# TinyX4.net
KiCad netlist of a schematic drawn in EAGLE
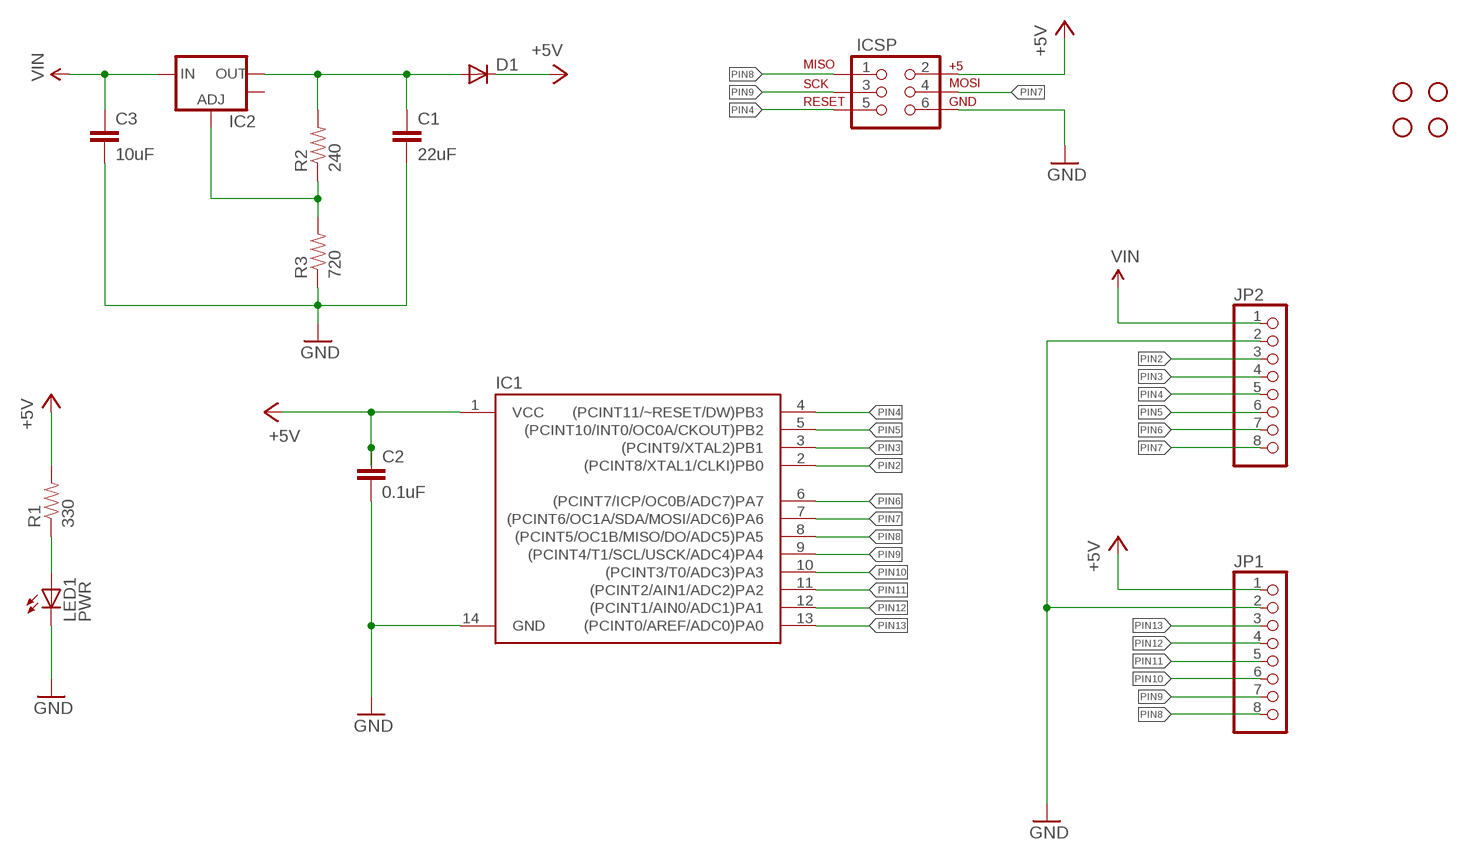
[diagram p0: schematic, sheet 1]

(export (version "E")
  (design (tool "Eeschema 10.0.6"))
  (components
    (comp (ref "C1")
      (value "22uF")
      (footprint "eagle-import:1206")
      (libsource (lib "eagle-import") (part "CAP1206"))
    )
    (comp (ref "C2")
      (value "0.1uF")
      (footprint "eagle-import:1206")
      (libsource (lib "eagle-import") (part "CAP1206"))
    )
    (comp (ref "C3")
      (value "10uF")
      (footprint "eagle-import:1206")
      (libsource (lib "eagle-import") (part "CAP1206"))
    )
    (comp (ref "D1")
      (value "DIODESOD")
      (footprint "eagle-import:SOD-323")
      (libsource (lib "eagle-import") (part "DIODESOD"))
    )
    (comp (ref "IC1")
      (value "ATTINY84ATTINY84-20PU")
      (footprint "eagle-import:DIL14")
      (libsource (lib "eagle-import") (part "ATTINY84ATTINY84-20PU"))
    )
    (comp (ref "IC2")
      (value "V_REG_LM1117SOT223")
      (footprint "eagle-import:SOT223")
      (libsource (lib "eagle-import") (part "V_REG_LM1117SOT223"))
    )
    (comp (ref "ICSP")
      (value "AVR_SPI_PRG_6PTH")
      (footprint "eagle-import:2X3")
      (libsource (lib "eagle-import") (part "AVR_SPI_PRG_6PTH"))
    )
    (comp (ref "JP1")
      (value "PINHD-1X8")
      (footprint "eagle-import:1X08")
      (libsource (lib "eagle-import") (part "PINHD-1X8"))
    )
    (comp (ref "JP2")
      (value "PINHD-1X8")
      (footprint "eagle-import:1X08")
      (libsource (lib "eagle-import") (part "PINHD-1X8"))
    )
    (comp (ref "LED1")
      (value "PWR")
      (footprint "eagle-import:LED-1206")
      (libsource (lib "eagle-import") (part "LED-RED1206"))
    )
    (comp (ref "R1")
      (value "330")
      (footprint "eagle-import:1206")
      (libsource (lib "eagle-import") (part "SparkFun-Resistors_RESISTOR1206"))
    )
    (comp (ref "R2")
      (value "240")
      (footprint "eagle-import:1206")
      (libsource (lib "eagle-import") (part "RESISTOR1206"))
    )
    (comp (ref "R3")
      (value "720")
      (footprint "eagle-import:1206")
      (libsource (lib "eagle-import") (part "RESISTOR1206"))
    )
    (comp (ref "STANDOFF1")
      (value "STAND-OFFTIGHT")
      (footprint "eagle-import:STAND-OFF-TIGHT")
      (libsource (lib "eagle-import") (part "STAND-OFFTIGHT"))
    )
    (comp (ref "STANDOFF2")
      (value "STAND-OFFTIGHT")
      (footprint "eagle-import:STAND-OFF-TIGHT")
      (libsource (lib "eagle-import") (part "STAND-OFFTIGHT"))
    )
    (comp (ref "STANDOFF3")
      (value "STAND-OFFTIGHT")
      (footprint "eagle-import:STAND-OFF-TIGHT")
      (libsource (lib "eagle-import") (part "STAND-OFFTIGHT"))
    )
    (comp (ref "STANDOFF4")
      (value "STAND-OFFTIGHT")
      (footprint "eagle-import:STAND-OFF-TIGHT")
      (libsource (lib "eagle-import") (part "STAND-OFFTIGHT"))
    )
  )
  (nets
    (net (code "1") (name "+5V") (class "Default")
      (node (ref "C2") (pin "1") (pinfunction "1_1") (pintype "passive"))
      (node (ref "D1") (pin "1") (pinfunction "C_1") (pintype "passive"))
      (node (ref "IC1") (pin "1") (pinfunction "VCC_1") (pintype "bidirectional"))
      (node (ref "ICSP") (pin "2") (pinfunction "2_2") (pintype "passive"))
      (node (ref "JP1") (pin "1") (pinfunction "1_1") (pintype "passive"))
      (node (ref "R1") (pin "2") (pinfunction "2_2") (pintype "passive"))
    )
    (net (code "2") (name "GND") (class "Default")
      (node (ref "C1") (pin "2") (pinfunction "2_2") (pintype "passive"))
      (node (ref "C2") (pin "2") (pinfunction "2_2") (pintype "passive"))
      (node (ref "C3") (pin "2") (pinfunction "2_2") (pintype "passive"))
      (node (ref "IC1") (pin "14") (pinfunction "GND_14") (pintype "bidirectional"))
      (node (ref "ICSP") (pin "6") (pinfunction "6_6") (pintype "passive"))
      (node (ref "JP1") (pin "2") (pinfunction "2_2") (pintype "passive"))
      (node (ref "JP2") (pin "2") (pinfunction "2_2") (pintype "passive"))
      (node (ref "LED1") (pin "C") (pinfunction "C_C") (pintype "passive"))
      (node (ref "R3") (pin "1") (pinfunction "1_1") (pintype "passive"))
    )
    (net (code "3") (name "Net-(D1-A)") (class "Default")
      (node (ref "C1") (pin "1") (pinfunction "1_1") (pintype "passive"))
      (node (ref "D1") (pin "2") (pinfunction "A_2") (pintype "passive"))
      (node (ref "IC2") (pin "2") (pinfunction "OUT_2") (pintype "output"))
      (node (ref "R2") (pin "2") (pinfunction "2_2") (pintype "passive"))
    )
    (net (code "4") (name "Net-(IC2-ADJ)") (class "Default")
      (node (ref "IC2") (pin "1") (pinfunction "ADJ_1") (pintype "input"))
      (node (ref "R2") (pin "1") (pinfunction "1_1") (pintype "passive"))
      (node (ref "R3") (pin "2") (pinfunction "2_2") (pintype "passive"))
    )
    (net (code "5") (name "Net-(LED1-PadA)") (class "Default")
      (node (ref "LED1") (pin "A") (pinfunction "A_A") (pintype "passive"))
      (node (ref "R1") (pin "1") (pinfunction "1_1") (pintype "passive"))
    )
    (net (code "6") (name "PIN2") (class "Default")
      (node (ref "IC1") (pin "2") (pinfunction "(PCINT8/XTAL1/CLKI)PB0_2") (pintype "bidirectional"))
      (node (ref "JP2") (pin "3") (pinfunction "3_3") (pintype "passive"))
    )
    (net (code "7") (name "PIN3") (class "Default")
      (node (ref "IC1") (pin "3") (pinfunction "(PCINT9/XTAL2)PB1_3") (pintype "bidirectional"))
      (node (ref "JP2") (pin "4") (pinfunction "4_4") (pintype "passive"))
    )
    (net (code "8") (name "PIN4") (class "Default")
      (node (ref "IC1") (pin "4") (pinfunction "(PCINT11/~{RESET/DW})PB3_4") (pintype "bidirectional"))
      (node (ref "ICSP") (pin "5") (pinfunction "5_5") (pintype "passive"))
      (node (ref "JP2") (pin "5") (pinfunction "5_5") (pintype "passive"))
    )
    (net (code "9") (name "PIN5") (class "Default")
      (node (ref "IC1") (pin "5") (pinfunction "(PCINT10/INT0/OC0A/CKOUT)PB2_5") (pintype "bidirectional"))
      (node (ref "JP2") (pin "6") (pinfunction "6_6") (pintype "passive"))
    )
    (net (code "10") (name "PIN6") (class "Default")
      (node (ref "IC1") (pin "6") (pinfunction "(PCINT7/ICP/OC0B/ADC7)PA7_6") (pintype "bidirectional"))
      (node (ref "JP2") (pin "7") (pinfunction "7_7") (pintype "passive"))
    )
    (net (code "11") (name "PIN7") (class "Default")
      (node (ref "IC1") (pin "7") (pinfunction "(PCINT6/OC1A/SDA/MOSI/ADC6)PA6_7") (pintype "bidirectional"))
      (node (ref "ICSP") (pin "4") (pinfunction "4_4") (pintype "passive"))
      (node (ref "JP2") (pin "8") (pinfunction "8_8") (pintype "passive"))
    )
    (net (code "12") (name "PIN8") (class "Default")
      (node (ref "IC1") (pin "8") (pinfunction "(PCINT5/OC1B/MISO/DO/ADC5)PA5_8") (pintype "bidirectional"))
      (node (ref "ICSP") (pin "1") (pinfunction "1_1") (pintype "passive"))
      (node (ref "JP1") (pin "8") (pinfunction "8_8") (pintype "passive"))
    )
    (net (code "13") (name "PIN9") (class "Default")
      (node (ref "IC1") (pin "9") (pinfunction "(PCINT4/T1/SCL/USCK/ADC4)PA4_9") (pintype "bidirectional"))
      (node (ref "ICSP") (pin "3") (pinfunction "3_3") (pintype "passive"))
      (node (ref "JP1") (pin "7") (pinfunction "7_7") (pintype "passive"))
    )
    (net (code "14") (name "PIN10") (class "Default")
      (node (ref "IC1") (pin "10") (pinfunction "(PCINT3/T0/ADC3)PA3_10") (pintype "bidirectional"))
      (node (ref "JP1") (pin "6") (pinfunction "6_6") (pintype "passive"))
    )
    (net (code "15") (name "PIN11") (class "Default")
      (node (ref "IC1") (pin "11") (pinfunction "(PCINT2/AIN1/ADC2)PA2_11") (pintype "bidirectional"))
      (node (ref "JP1") (pin "5") (pinfunction "5_5") (pintype "passive"))
    )
    (net (code "16") (name "PIN12") (class "Default")
      (node (ref "IC1") (pin "12") (pinfunction "(PCINT1/AIN0/ADC1)PA1_12") (pintype "bidirectional"))
      (node (ref "JP1") (pin "4") (pinfunction "4_4") (pintype "passive"))
    )
    (net (code "17") (name "PIN13") (class "Default")
      (node (ref "IC1") (pin "13") (pinfunction "(PCINT0/AREF/ADC0)PA0_13") (pintype "bidirectional"))
      (node (ref "JP1") (pin "3") (pinfunction "3_3") (pintype "passive"))
    )
    (net (code "18") (name "VIN") (class "Default")
      (node (ref "C3") (pin "1") (pinfunction "1_1") (pintype "passive"))
      (node (ref "IC2") (pin "3") (pinfunction "IN_3") (pintype "input"))
      (node (ref "JP2") (pin "1") (pinfunction "1_1") (pintype "passive"))
    )
    (net (code "19") (name "unconnected-(IC2-OUT-Pad4)") (class "Default")
      (node (ref "IC2") (pin "4") (pinfunction "OUT_4") (pintype "output"))
    )
  )
)
